# EXT_M_V1.net
KiCad netlist of a schematic drawn in Altium Designer
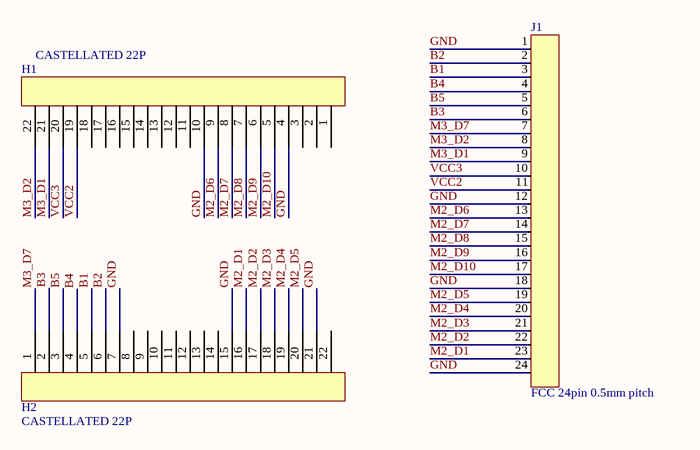
[diagram p0: EXT_M_V1.SchDoc]

(export (version "E")
  (design (tool "Eeschema 10.0.6"))
  (components
    (comp (ref "H1")
      (value "CASTELLATED 22P")
      (footprint "CASTELLATED 22P")
      (libsource (lib "USIB") (part "CASTELLATED 22P"))
    )
    (comp (ref "H2")
      (value "CASTELLATED 22P")
      (footprint "CASTELLATED 22P")
      (libsource (lib "") (part "CASTELLATED 22P_1"))
    )
    (comp (ref "J1")
      (value "FCC 24pin 0.5mm pitch")
      (footprint "FCC_24P_0.5MM")
      (libsource (lib "FCC") (part "FCC_24P_0.5MM"))
    )
  )
  (nets
    (net (code "1") (name "/B1") (class "Default")
      (node (ref "H2") (pin "5") (pintype "passive"))
      (node (ref "J1") (pin "3") (pintype "input"))
    )
    (net (code "2") (name "/B2") (class "Default")
      (node (ref "H2") (pin "6") (pintype "passive"))
      (node (ref "J1") (pin "2") (pintype "input"))
    )
    (net (code "3") (name "/B3") (class "Default")
      (node (ref "H2") (pin "2") (pintype "passive"))
      (node (ref "J1") (pin "6") (pintype "input"))
    )
    (net (code "4") (name "/B4") (class "Default")
      (node (ref "H2") (pin "4") (pintype "passive"))
      (node (ref "J1") (pin "4") (pintype "input"))
    )
    (net (code "5") (name "/B5") (class "Default")
      (node (ref "H2") (pin "3") (pintype "passive"))
      (node (ref "J1") (pin "5") (pintype "input"))
    )
    (net (code "6") (name "/GND") (class "Default")
      (node (ref "H1") (pin "10") (pintype "passive"))
      (node (ref "H1") (pin "4") (pintype "passive"))
      (node (ref "H2") (pin "15") (pintype "passive"))
      (node (ref "H2") (pin "21") (pintype "passive"))
      (node (ref "H2") (pin "7") (pintype "passive"))
      (node (ref "J1") (pin "1") (pintype "input"))
      (node (ref "J1") (pin "12") (pintype "input"))
      (node (ref "J1") (pin "18") (pintype "input"))
      (node (ref "J1") (pin "24") (pintype "input"))
    )
    (net (code "7") (name "/M2_D1") (class "Default")
      (node (ref "H2") (pin "16") (pintype "passive"))
      (node (ref "J1") (pin "23") (pintype "input"))
    )
    (net (code "8") (name "/M2_D2") (class "Default")
      (node (ref "H2") (pin "17") (pintype "passive"))
      (node (ref "J1") (pin "22") (pintype "input"))
    )
    (net (code "9") (name "/M2_D3") (class "Default")
      (node (ref "H2") (pin "18") (pintype "passive"))
      (node (ref "J1") (pin "21") (pintype "input"))
    )
    (net (code "10") (name "/M2_D4") (class "Default")
      (node (ref "H2") (pin "19") (pintype "passive"))
      (node (ref "J1") (pin "20") (pintype "input"))
    )
    (net (code "11") (name "/M2_D5") (class "Default")
      (node (ref "H2") (pin "20") (pintype "passive"))
      (node (ref "J1") (pin "19") (pintype "input"))
    )
    (net (code "12") (name "/M2_D6") (class "Default")
      (node (ref "H1") (pin "9") (pintype "passive"))
      (node (ref "J1") (pin "13") (pintype "input"))
    )
    (net (code "13") (name "/M2_D7") (class "Default")
      (node (ref "H1") (pin "8") (pintype "passive"))
      (node (ref "J1") (pin "14") (pintype "input"))
    )
    (net (code "14") (name "/M2_D8") (class "Default")
      (node (ref "H1") (pin "7") (pintype "passive"))
      (node (ref "J1") (pin "15") (pintype "input"))
    )
    (net (code "15") (name "/M2_D9") (class "Default")
      (node (ref "H1") (pin "6") (pintype "passive"))
      (node (ref "J1") (pin "16") (pintype "input"))
    )
    (net (code "16") (name "/M2_D10") (class "Default")
      (node (ref "H1") (pin "5") (pintype "passive"))
      (node (ref "J1") (pin "17") (pintype "input"))
    )
    (net (code "17") (name "/M3_D1") (class "Default")
      (node (ref "H1") (pin "21") (pintype "passive"))
      (node (ref "J1") (pin "9") (pintype "input"))
    )
    (net (code "18") (name "/M3_D2") (class "Default")
      (node (ref "H1") (pin "22") (pintype "passive"))
      (node (ref "J1") (pin "8") (pintype "input"))
    )
    (net (code "19") (name "/M3_D7") (class "Default")
      (node (ref "H2") (pin "1") (pintype "passive"))
      (node (ref "J1") (pin "7") (pintype "input"))
    )
    (net (code "20") (name "/VCC2") (class "Default")
      (node (ref "H1") (pin "19") (pintype "passive"))
      (node (ref "J1") (pin "11") (pintype "input"))
    )
    (net (code "21") (name "/VCC3") (class "Default")
      (node (ref "H1") (pin "20") (pintype "passive"))
      (node (ref "J1") (pin "10") (pintype "input"))
    )
    (net (code "22") (name "unconnected-(H1-Pad1)") (class "Default")
      (node (ref "H1") (pin "1") (pintype "passive"))
    )
    (net (code "23") (name "unconnected-(H1-Pad2)") (class "Default")
      (node (ref "H1") (pin "2") (pintype "passive"))
    )
    (net (code "24") (name "unconnected-(H1-Pad3)") (class "Default")
      (node (ref "H1") (pin "3") (pintype "passive"))
    )
    (net (code "25") (name "unconnected-(H1-Pad11)") (class "Default")
      (node (ref "H1") (pin "11") (pintype "passive"))
    )
    (net (code "26") (name "unconnected-(H1-Pad12)") (class "Default")
      (node (ref "H1") (pin "12") (pintype "passive"))
    )
    (net (code "27") (name "unconnected-(H1-Pad13)") (class "Default")
      (node (ref "H1") (pin "13") (pintype "passive"))
    )
    (net (code "28") (name "unconnected-(H1-Pad14)") (class "Default")
      (node (ref "H1") (pin "14") (pintype "passive"))
    )
    (net (code "29") (name "unconnected-(H1-Pad15)") (class "Default")
      (node (ref "H1") (pin "15") (pintype "passive"))
    )
    (net (code "30") (name "unconnected-(H1-Pad16)") (class "Default")
      (node (ref "H1") (pin "16") (pintype "passive"))
    )
    (net (code "31") (name "unconnected-(H1-Pad17)") (class "Default")
      (node (ref "H1") (pin "17") (pintype "passive"))
    )
    (net (code "32") (name "unconnected-(H1-Pad18)") (class "Default")
      (node (ref "H1") (pin "18") (pintype "passive"))
    )
    (net (code "33") (name "unconnected-(H2-Pad8)") (class "Default")
      (node (ref "H2") (pin "8") (pintype "passive"))
    )
    (net (code "34") (name "unconnected-(H2-Pad9)") (class "Default")
      (node (ref "H2") (pin "9") (pintype "passive"))
    )
    (net (code "35") (name "unconnected-(H2-Pad10)") (class "Default")
      (node (ref "H2") (pin "10") (pintype "passive"))
    )
    (net (code "36") (name "unconnected-(H2-Pad11)") (class "Default")
      (node (ref "H2") (pin "11") (pintype "passive"))
    )
    (net (code "37") (name "unconnected-(H2-Pad12)") (class "Default")
      (node (ref "H2") (pin "12") (pintype "passive"))
    )
    (net (code "38") (name "unconnected-(H2-Pad13)") (class "Default")
      (node (ref "H2") (pin "13") (pintype "passive"))
    )
    (net (code "39") (name "unconnected-(H2-Pad14)") (class "Default")
      (node (ref "H2") (pin "14") (pintype "passive"))
    )
    (net (code "40") (name "unconnected-(H2-Pad22)") (class "Default")
      (node (ref "H2") (pin "22") (pintype "passive"))
    )
  )
)
